# RPi-HAT_BUS-Controller_V0_9c.net
KiCad netlist of a schematic drawn in EAGLE
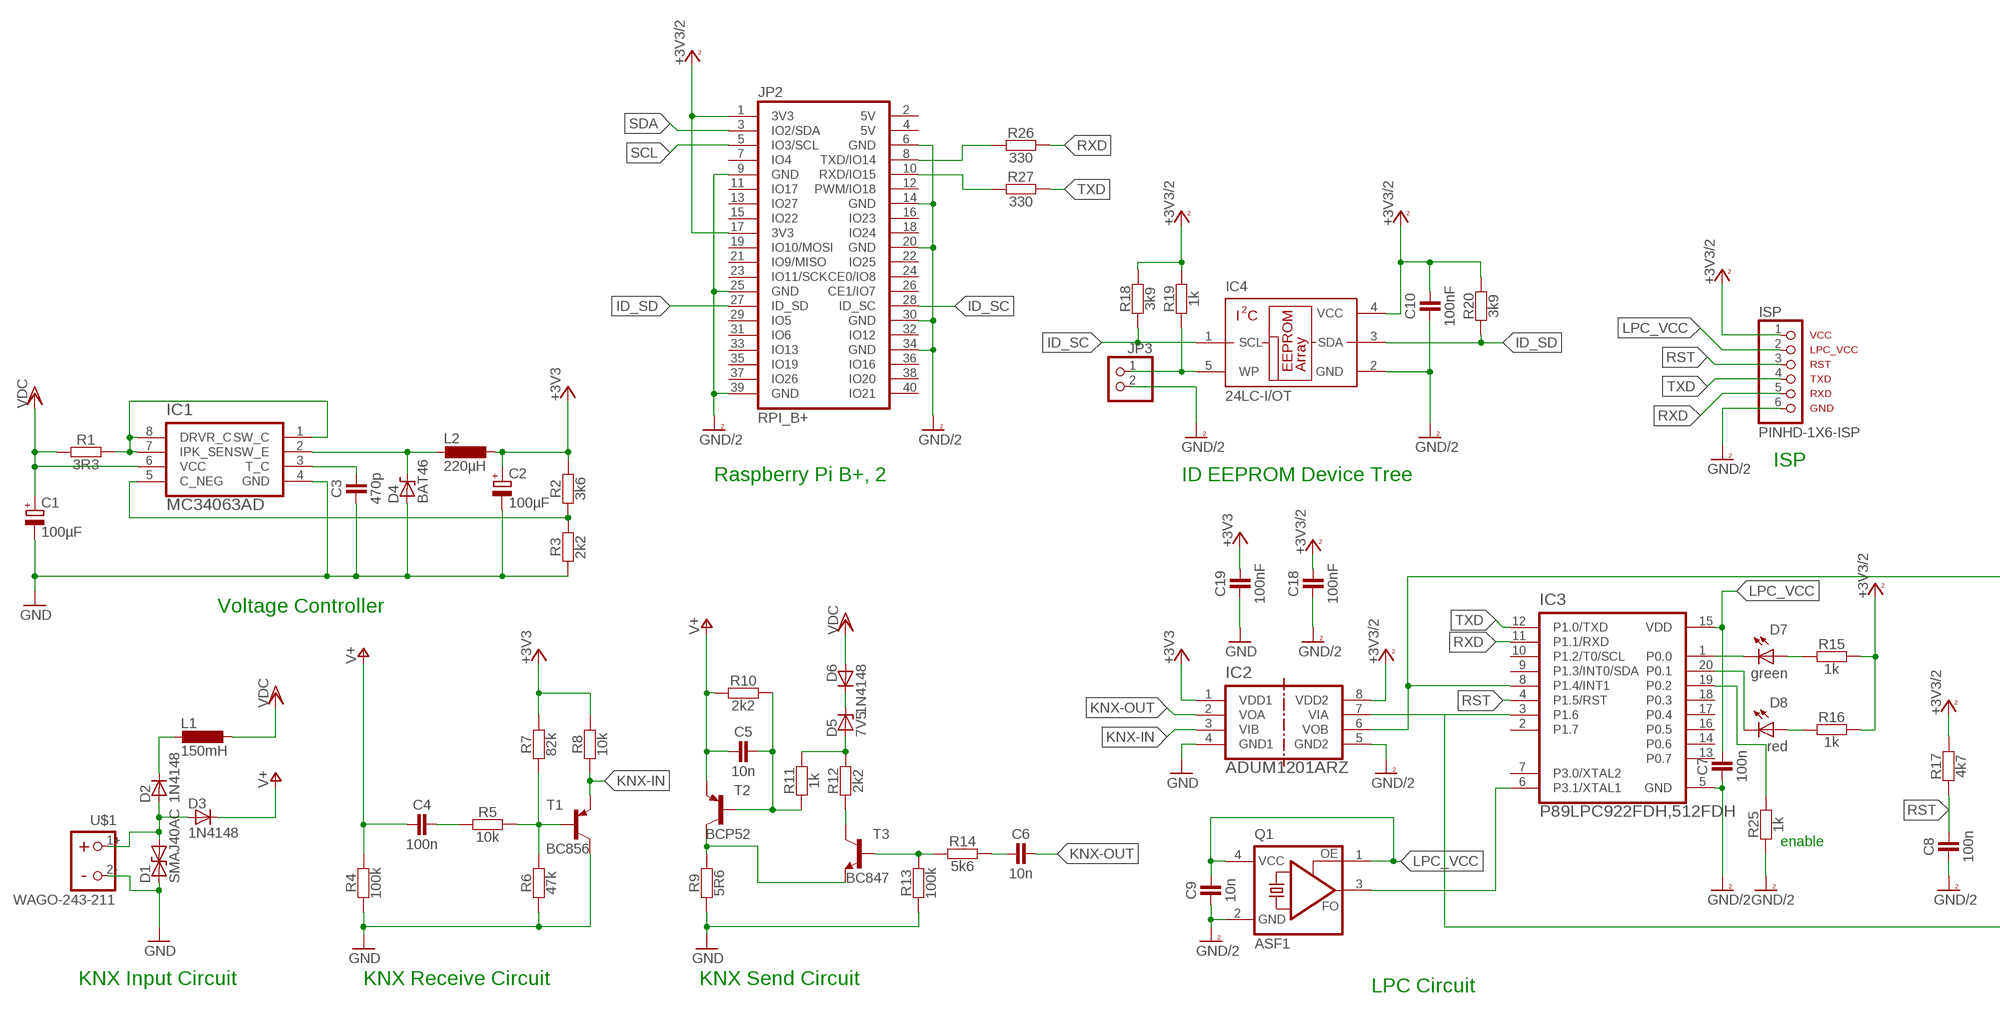
[diagram p0: schematic, sheet 1, part 1 of 2]
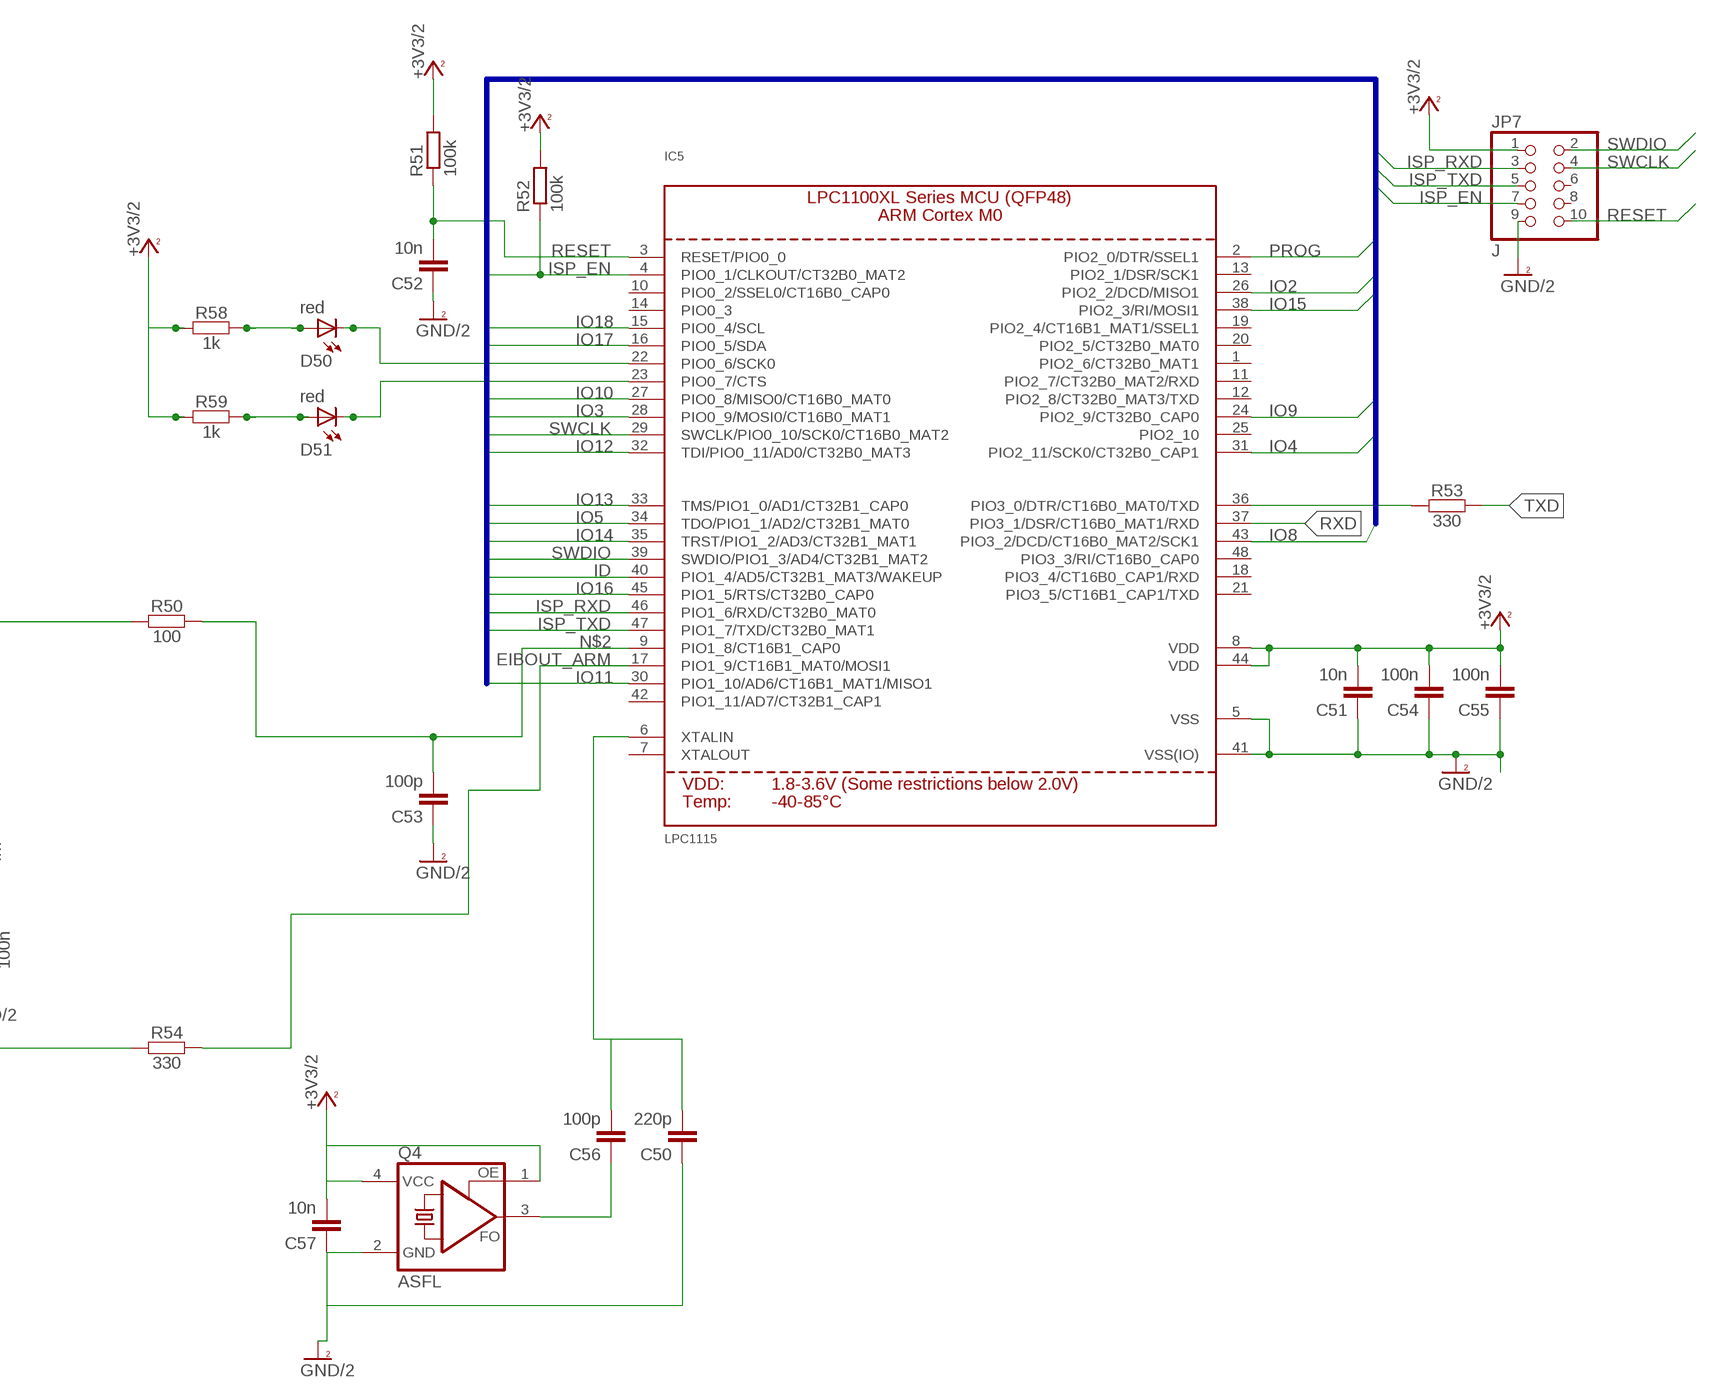
[diagram p1: schematic, sheet 1, part 2 of 2]

(export (version "E")
  (design (tool "Eeschema 10.0.6"))
  (components
    (comp (ref "C1")
      (value "100µF")
      (footprint "eagle-import:PANASONIC_D")
      (libsource (lib "eagle-import") (part "100µF,35V"))
    )
    (comp (ref "C2")
      (value "100µF")
      (footprint "eagle-import:PANASONIC_C")
      (libsource (lib "eagle-import") (part "100µF,6.3V"))
    )
    (comp (ref "C3")
      (value "470p")
      (footprint "eagle-import:R1206")
      (libsource (lib "eagle-import") (part "CAPACITORC1206"))
    )
    (comp (ref "C4")
      (value "100n")
      (footprint "eagle-import:R1206")
      (libsource (lib "eagle-import") (part "CAPACITORC1206"))
    )
    (comp (ref "C5")
      (value "10n")
      (footprint "eagle-import:R1206")
      (libsource (lib "eagle-import") (part "CAPACITORC1206"))
    )
    (comp (ref "C6")
      (value "10n")
      (footprint "eagle-import:R1206")
      (libsource (lib "eagle-import") (part "CAPACITORC1206"))
    )
    (comp (ref "C7")
      (value "100n")
      (footprint "eagle-import:R1206")
      (libsource (lib "eagle-import") (part "CAPACITORC1206"))
    )
    (comp (ref "C8")
      (value "100n")
      (footprint "eagle-import:R1206")
      (libsource (lib "eagle-import") (part "CAPACITORC1206"))
    )
    (comp (ref "C9")
      (value "10n")
      (footprint "eagle-import:R1206")
      (libsource (lib "eagle-import") (part "CAPACITORC1206"))
    )
    (comp (ref "C10")
      (value "100nF")
      (footprint "eagle-import:R1206")
      (libsource (lib "eagle-import") (part "CAPACITORC1206"))
    )
    (comp (ref "C18")
      (value "100nF")
      (footprint "eagle-import:R1206")
      (libsource (lib "eagle-import") (part "CAPACITORC1206"))
    )
    (comp (ref "C19")
      (value "100nF")
      (footprint "eagle-import:R1206")
      (libsource (lib "eagle-import") (part "CAPACITORC1206"))
    )
    (comp (ref "C50")
      (value "220p")
      (footprint "eagle-import:C1206")
      (libsource (lib "eagle-import") (part "C-EUC1206"))
    )
    (comp (ref "C51")
      (value "10n")
      (footprint "eagle-import:C1206")
      (libsource (lib "eagle-import") (part "C-EUC1206"))
    )
    (comp (ref "C52")
      (value "10n")
      (footprint "eagle-import:C1206")
      (libsource (lib "eagle-import") (part "C-EUC1206"))
    )
    (comp (ref "C53")
      (value "100p")
      (footprint "eagle-import:C1206")
      (libsource (lib "eagle-import") (part "C-EUC1206"))
    )
    (comp (ref "C54")
      (value "100n")
      (footprint "eagle-import:C1206")
      (libsource (lib "eagle-import") (part "C-EUC1206"))
    )
    (comp (ref "C55")
      (value "100n")
      (footprint "eagle-import:C1206")
      (libsource (lib "eagle-import") (part "C-EUC1206"))
    )
    (comp (ref "C56")
      (value "100p")
      (footprint "eagle-import:C1206")
      (libsource (lib "eagle-import") (part "C-EUC1206"))
    )
    (comp (ref "C57")
      (value "10n")
      (footprint "eagle-import:C1206")
      (libsource (lib "eagle-import") (part "C-EUC1206"))
    )
    (comp (ref "D1")
      (value "SMAJ40AC")
      (footprint "eagle-import:DO-214AC")
      (libsource (lib "eagle-import") (part "SMAJ40AC"))
    )
    (comp (ref "D2")
      (value "1N4148")
      (footprint "eagle-import:MINIMELF")
      (libsource (lib "eagle-import") (part "1N4148MINIMELF"))
    )
    (comp (ref "D3")
      (value "1N4148")
      (footprint "eagle-import:MINIMELF")
      (libsource (lib "eagle-import") (part "1N4148MINIMELF"))
    )
    (comp (ref "D4")
      (value "BAT46")
      (footprint "eagle-import:MINIMELF")
      (libsource (lib "eagle-import") (part "BAT46"))
    )
    (comp (ref "D5")
      (value "7V5")
      (footprint "eagle-import:MINIMELF")
      (libsource (lib "eagle-import") (part "Z-DIODE"))
    )
    (comp (ref "D6")
      (value "1N4148")
      (footprint "eagle-import:MINIMELF")
      (libsource (lib "eagle-import") (part "Diode_for_Selfbus-Projects_1N4148MINIMELF"))
    )
    (comp (ref "D7")
      (value "green")
      (footprint "eagle-import:CHIPLED_1206")
      (libsource (lib "eagle-import") (part "LED1206"))
    )
    (comp (ref "D8")
      (value "red")
      (footprint "eagle-import:CHIPLED_1206")
      (libsource (lib "eagle-import") (part "LED1206"))
    )
    (comp (ref "D50")
      (value "red")
      (footprint "eagle-import:CHIPLED_1206")
      (libsource (lib "eagle-import") (part "LED1206"))
    )
    (comp (ref "D51")
      (value "red")
      (footprint "eagle-import:CHIPLED_1206")
      (libsource (lib "eagle-import") (part "LED1206"))
    )
    (comp (ref "IC1")
      (value "MC34063AD")
      (footprint "eagle-import:SOIC127P600X175-8N")
      (libsource (lib "eagle-import") (part "MC34063AD"))
    )
    (comp (ref "IC2")
      (value "ADUM1201ARZ")
      (footprint "eagle-import:SOIC127P600X175-8N")
      (libsource (lib "eagle-import") (part "ADUM1201ARZ"))
    )
    (comp (ref "IC3")
      (value "P89LPC922FDH,512FDH")
      (footprint "eagle-import:SOP65P640X110-20N")
      (fields (field (name "MPN") "P89LPC922FDH,512"))
      (libsource (lib "eagle-import") (part "P89LPC922FDH,512FDH"))
    )
    (comp (ref "IC4")
      (value "24LC-I/OT")
      (footprint "eagle-import:SOT23-5")
      (libsource (lib "eagle-import") (part "24LC-I/OT"))
    )
    (comp (ref "IC5")
      (value "LPC1115")
      (footprint "eagle-import:LQFP48")
      (libsource (lib "eagle-import") (part "LPC1113/4/5_QFP48_XLSERIES"))
    )
    (comp (ref "ISP")
      (value "PINHD-1X6-ISP")
      (footprint "eagle-import:1X06")
      (libsource (lib "eagle-import") (part "PINHD-1X6-ISP"))
    )
    (comp (ref "JP2")
      (value "RPI_B+")
      (footprint "eagle-import:RPI-B+HAT")
      (libsource (lib "eagle-import") (part "RPI_B+"))
    )
    (comp (ref "JP3")
      (value "PINHD-1X2")
      (footprint "eagle-import:1X02")
      (libsource (lib "eagle-import") (part "PINHD-1X2"))
    )
    (comp (ref "JP7")
      (value "J")
      (footprint "eagle-import:2X05M")
      (libsource (lib "eagle-import") (part "PINHD-2X05_2.00"))
    )
    (comp (ref "L1")
      (value "150mH")
      (footprint "eagle-import:11P-L1")
      (libsource (lib "eagle-import") (part "150MH-L11PL1"))
    )
    (comp (ref "L2")
      (value "220µH")
      (footprint "eagle-import:2200-11.43")
      (libsource (lib "eagle-import") (part "220µH-SMCC11.43"))
    )
    (comp (ref "Q1")
      (value "ASF1")
      (footprint "eagle-import:ASF")
      (libsource (lib "eagle-import") (part "ASF1"))
    )
    (comp (ref "Q4")
      (value "ASFL")
      (footprint "eagle-import:ASF")
      (fields (field (name "MPN") "ASFLM1-50.000MHZ-C-T"))
      (libsource (lib "eagle-import") (part "crystal_ASFL"))
    )
    (comp (ref "R1")
      (value "3R3")
      (footprint "eagle-import:R1206")
      (libsource (lib "eagle-import") (part "RESISTORR1206"))
    )
    (comp (ref "R2")
      (value "3k6")
      (footprint "eagle-import:R1206")
      (libsource (lib "eagle-import") (part "RESISTORR1206"))
    )
    (comp (ref "R3")
      (value "2k2")
      (footprint "eagle-import:R1206")
      (libsource (lib "eagle-import") (part "RESISTORR1206"))
    )
    (comp (ref "R4")
      (value "100k")
      (footprint "eagle-import:R1206")
      (libsource (lib "eagle-import") (part "RESISTORR1206"))
    )
    (comp (ref "R5")
      (value "10k")
      (footprint "eagle-import:R1206")
      (libsource (lib "eagle-import") (part "RESISTORR1206"))
    )
    (comp (ref "R6")
      (value "47k")
      (footprint "eagle-import:R1206")
      (libsource (lib "eagle-import") (part "RESISTORR1206"))
    )
    (comp (ref "R7")
      (value "82k")
      (footprint "eagle-import:R1206")
      (libsource (lib "eagle-import") (part "RESISTORR1206"))
    )
    (comp (ref "R8")
      (value "10k")
      (footprint "eagle-import:R1206")
      (libsource (lib "eagle-import") (part "RESISTORR1206"))
    )
    (comp (ref "R9")
      (value "5R6")
      (footprint "eagle-import:R1206")
      (libsource (lib "eagle-import") (part "RESISTORR1206"))
    )
    (comp (ref "R10")
      (value "2k2")
      (footprint "eagle-import:R1206")
      (libsource (lib "eagle-import") (part "RESISTORR1206"))
    )
    (comp (ref "R11")
      (value "1k")
      (footprint "eagle-import:R1206")
      (libsource (lib "eagle-import") (part "RESISTORR1206"))
    )
    (comp (ref "R12")
      (value "2k2")
      (footprint "eagle-import:R1206")
      (libsource (lib "eagle-import") (part "RESISTORR1206"))
    )
    (comp (ref "R13")
      (value "100k")
      (footprint "eagle-import:R1206")
      (libsource (lib "eagle-import") (part "RESISTORR1206"))
    )
    (comp (ref "R14")
      (value "5k6")
      (footprint "eagle-import:R1206")
      (libsource (lib "eagle-import") (part "RESISTORR1206"))
    )
    (comp (ref "R15")
      (value "1k")
      (footprint "eagle-import:R1206")
      (libsource (lib "eagle-import") (part "RESISTORR1206"))
    )
    (comp (ref "R16")
      (value "1k")
      (footprint "eagle-import:R1206")
      (libsource (lib "eagle-import") (part "RESISTORR1206"))
    )
    (comp (ref "R17")
      (value "4k7")
      (footprint "eagle-import:R1206")
      (libsource (lib "eagle-import") (part "RESISTORR1206"))
    )
    (comp (ref "R18")
      (value "3k9")
      (footprint "eagle-import:R1206")
      (libsource (lib "eagle-import") (part "RESISTORR1206"))
    )
    (comp (ref "R19")
      (value "1k")
      (footprint "eagle-import:R1206")
      (libsource (lib "eagle-import") (part "RESISTORR1206"))
    )
    (comp (ref "R20")
      (value "3k9")
      (footprint "eagle-import:R1206")
      (libsource (lib "eagle-import") (part "RESISTORR1206"))
    )
    (comp (ref "R25")
      (value "1k")
      (footprint "eagle-import:R1206")
      (libsource (lib "eagle-import") (part "RESISTORR1206"))
    )
    (comp (ref "R26")
      (value "330")
      (footprint "eagle-import:R1206")
      (libsource (lib "eagle-import") (part "RESISTORR1206"))
    )
    (comp (ref "R27")
      (value "330")
      (footprint "eagle-import:R1206")
      (libsource (lib "eagle-import") (part "RESISTORR1206"))
    )
    (comp (ref "R50")
      (value "100")
      (footprint "eagle-import:R1206")
      (libsource (lib "eagle-import") (part "RESISTORR1206"))
    )
    (comp (ref "R51")
      (value "100k")
      (footprint "eagle-import:R1206")
      (libsource (lib "eagle-import") (part "R-EU_R1206"))
    )
    (comp (ref "R52")
      (value "100k")
      (footprint "eagle-import:R1206")
      (libsource (lib "eagle-import") (part "R-EU_R1206"))
    )
    (comp (ref "R53")
      (value "330")
      (footprint "eagle-import:R1206")
      (libsource (lib "eagle-import") (part "RESISTORR1206"))
    )
    (comp (ref "R54")
      (value "330")
      (footprint "eagle-import:R1206")
      (libsource (lib "eagle-import") (part "RESISTORR1206"))
    )
    (comp (ref "R58")
      (value "1k")
      (footprint "eagle-import:R1206")
      (libsource (lib "eagle-import") (part "RESISTORR1206"))
    )
    (comp (ref "R59")
      (value "1k")
      (footprint "eagle-import:R1206")
      (libsource (lib "eagle-import") (part "RESISTORR1206"))
    )
    (comp (ref "T1")
      (value "BC856")
      (footprint "eagle-import:SOT23")
      (libsource (lib "eagle-import") (part "PNPBC856"))
    )
    (comp (ref "T2")
      (value "BCP52")
      (footprint "eagle-import:SOT223")
      (libsource (lib "eagle-import") (part "PNPBCP52"))
    )
    (comp (ref "T3")
      (value "BC847")
      (footprint "eagle-import:SOT23")
      (libsource (lib "eagle-import") (part "NPN-BC847"))
    )
    (comp (ref "U$1")
      (value "WAGO-243-211")
      (footprint "eagle-import:WAGO-243-211")
      (libsource (lib "eagle-import") (part "WAGO-243-211"))
    )
  )
  (nets
    (net (code "1") (name "+3V3") (class "Default")
      (node (ref "C19") (pin "2") (pinfunction "2_2") (pintype "passive"))
      (node (ref "C2") (pin "+") (pinfunction "+_+") (pintype "passive"))
      (node (ref "IC2") (pin "1") (pinfunction "VDD1_1") (pintype "power_in"))
      (node (ref "L2") (pin "1") (pinfunction "1_1") (pintype "passive"))
      (node (ref "R2") (pin "2") (pinfunction "2_2") (pintype "passive"))
      (node (ref "R7") (pin "2") (pinfunction "2_2") (pintype "passive"))
      (node (ref "R8") (pin "2") (pinfunction "2_2") (pintype "passive"))
    )
    (net (code "2") (name "+3V3{slash}2") (class "Default")
      (node (ref "C10") (pin "2") (pinfunction "2_2") (pintype "passive"))
      (node (ref "C18") (pin "2") (pinfunction "2_2") (pintype "passive"))
      (node (ref "C51") (pin "2") (pinfunction "2_2") (pintype "passive"))
      (node (ref "C54") (pin "2") (pinfunction "2_2") (pintype "passive"))
      (node (ref "C55") (pin "2") (pinfunction "2_2") (pintype "passive"))
      (node (ref "C57") (pin "2") (pinfunction "2_2") (pintype "passive"))
      (node (ref "IC2") (pin "8") (pinfunction "VDD2_8") (pintype "power_in"))
      (node (ref "IC4") (pin "4") (pinfunction "VCC_4") (pintype "power_in"))
      (node (ref "IC5") (pin "44") (pinfunction "VDD_44") (pintype "power_in"))
      (node (ref "IC5") (pin "8") (pinfunction "VDD_8") (pintype "power_in"))
      (node (ref "ISP") (pin "1") (pinfunction "1_1") (pintype "passive"))
      (node (ref "JP2") (pin "1") (pinfunction "3V3_1") (pintype "passive"))
      (node (ref "JP2") (pin "17") (pinfunction "3V3_17") (pintype "passive"))
      (node (ref "JP7") (pin "1") (pinfunction "1_1") (pintype "passive"))
      (node (ref "Q4") (pin "1") (pinfunction "OE_1") (pintype "input"))
      (node (ref "Q4") (pin "4") (pinfunction "VCC_4") (pintype "power_in"))
      (node (ref "R15") (pin "2") (pinfunction "2_2") (pintype "passive"))
      (node (ref "R16") (pin "2") (pinfunction "2_2") (pintype "passive"))
      (node (ref "R17") (pin "2") (pinfunction "2_2") (pintype "passive"))
      (node (ref "R18") (pin "2") (pinfunction "2_2") (pintype "passive"))
      (node (ref "R19") (pin "2") (pinfunction "2_2") (pintype "passive"))
      (node (ref "R20") (pin "2") (pinfunction "2_2") (pintype "passive"))
      (node (ref "R51") (pin "2") (pinfunction "2_2") (pintype "passive"))
      (node (ref "R52") (pin "2") (pinfunction "2_2") (pintype "passive"))
      (node (ref "R58") (pin "1") (pinfunction "1_1") (pintype "passive"))
      (node (ref "R59") (pin "1") (pinfunction "1_1") (pintype "passive"))
    )
    (net (code "3") (name "/EIBOUT_ARM") (class "Default")
      (node (ref "IC5") (pin "17") (pinfunction "PIO1_9/CT16B1_MAT0/MOSI1_17") (pintype "bidirectional"))
      (node (ref "R54") (pin "2") (pinfunction "2_2") (pintype "passive"))
    )
    (net (code "4") (name "/ID") (class "Default")
      (node (ref "IC5") (pin "40") (pinfunction "PIO1_4/AD5/CT32B1_MAT3/WAKEUP_40") (pintype "bidirectional"))
    )
    (net (code "5") (name "/IO2") (class "Default")
      (node (ref "IC5") (pin "26") (pinfunction "PIO2_2/DCD/MISO1_26") (pintype "bidirectional"))
    )
    (net (code "6") (name "/IO3") (class "Default")
      (node (ref "IC5") (pin "28") (pinfunction "PIO0_9/MOSI0/CT16B0_MAT1_28") (pintype "bidirectional"))
    )
    (net (code "7") (name "/IO4") (class "Default")
      (node (ref "IC5") (pin "31") (pinfunction "PIO2_11/SCK0/CT32B0_CAP1_31") (pintype "bidirectional"))
    )
    (net (code "8") (name "/IO5") (class "Default")
      (node (ref "IC5") (pin "34") (pinfunction "TDO/PIO1_1/AD2/CT32B1_MAT0_34") (pintype "bidirectional"))
    )
    (net (code "9") (name "/IO8") (class "Default")
      (node (ref "IC5") (pin "43") (pinfunction "PIO3_2/DCD/CT16B0_MAT2/SCK1_43") (pintype "bidirectional"))
    )
    (net (code "10") (name "/IO9") (class "Default")
      (node (ref "IC5") (pin "24") (pinfunction "PIO2_9/CT32B0_CAP0_24") (pintype "bidirectional"))
    )
    (net (code "11") (name "/IO10") (class "Default")
      (node (ref "IC5") (pin "27") (pinfunction "PIO0_8/MISO0/CT16B0_MAT0_27") (pintype "bidirectional"))
    )
    (net (code "12") (name "/IO11") (class "Default")
      (node (ref "IC5") (pin "30") (pinfunction "PIO1_10/AD6/CT16B1_MAT1/MISO1_30") (pintype "bidirectional"))
    )
    (net (code "13") (name "/IO12") (class "Default")
      (node (ref "IC5") (pin "32") (pinfunction "TDI/PIO0_11/AD0/CT32B0_MAT3_32") (pintype "bidirectional"))
    )
    (net (code "14") (name "/IO13") (class "Default")
      (node (ref "IC5") (pin "33") (pinfunction "TMS/PIO1_0/AD1/CT32B1_CAP0_33") (pintype "bidirectional"))
    )
    (net (code "15") (name "/IO14") (class "Default")
      (node (ref "IC5") (pin "35") (pinfunction "TRST/PIO1_2/AD3/CT32B1_MAT1_35") (pintype "bidirectional"))
    )
    (net (code "16") (name "/IO15") (class "Default")
      (node (ref "IC5") (pin "38") (pinfunction "PIO2_3/RI/MOSI1_38") (pintype "bidirectional"))
    )
    (net (code "17") (name "/IO16") (class "Default")
      (node (ref "IC5") (pin "45") (pinfunction "PIO1_5/RTS/CT32B0_CAP0_45") (pintype "bidirectional"))
    )
    (net (code "18") (name "/IO17") (class "Default")
      (node (ref "IC5") (pin "16") (pinfunction "PIO0_5/SDA_16") (pintype "bidirectional"))
    )
    (net (code "19") (name "/IO18") (class "Default")
      (node (ref "IC5") (pin "15") (pinfunction "PIO0_4/SCL_15") (pintype "bidirectional"))
    )
    (net (code "20") (name "/ISP_EN") (class "Default")
      (node (ref "IC5") (pin "4") (pinfunction "PIO0_1/CLKOUT/CT32B0_MAT2_4") (pintype "bidirectional"))
      (node (ref "JP7") (pin "7") (pinfunction "7_7") (pintype "passive"))
      (node (ref "R52") (pin "1") (pinfunction "1_1") (pintype "passive"))
    )
    (net (code "21") (name "/ISP_RXD") (class "Default")
      (node (ref "IC5") (pin "46") (pinfunction "PIO1_6/RXD/CT32B0_MAT0_46") (pintype "bidirectional"))
      (node (ref "JP7") (pin "3") (pinfunction "3_3") (pintype "passive"))
    )
    (net (code "22") (name "/ISP_TXD") (class "Default")
      (node (ref "IC5") (pin "47") (pinfunction "PIO1_7/TXD/CT32B0_MAT1_47") (pintype "bidirectional"))
      (node (ref "JP7") (pin "5") (pinfunction "5_5") (pintype "passive"))
    )
    (net (code "23") (name "/N$2") (class "Default")
      (node (ref "C53") (pin "2") (pinfunction "2_2") (pintype "passive"))
      (node (ref "IC5") (pin "9") (pinfunction "PIO1_8/CT16B1_CAP0_9") (pintype "bidirectional"))
      (node (ref "R50") (pin "2") (pinfunction "2_2") (pintype "passive"))
    )
    (net (code "24") (name "/PROG") (class "Default")
      (node (ref "IC5") (pin "2") (pinfunction "PIO2_0/DTR/SSEL1_2") (pintype "bidirectional"))
    )
    (net (code "25") (name "/RESET") (class "Default")
      (node (ref "C52") (pin "2") (pinfunction "2_2") (pintype "passive"))
      (node (ref "IC5") (pin "3") (pinfunction "RESET/PIO0_0_3") (pintype "bidirectional"))
      (node (ref "JP7") (pin "10") (pinfunction "10_10") (pintype "passive"))
      (node (ref "R51") (pin "1") (pinfunction "1_1") (pintype "passive"))
    )
    (net (code "26") (name "/SWCLK") (class "Default")
      (node (ref "IC5") (pin "29") (pinfunction "SWCLK/PIO0_10/SCK0/CT16B0_MAT2_29") (pintype "bidirectional"))
      (node (ref "JP7") (pin "4") (pinfunction "4_4") (pintype "passive"))
    )
    (net (code "27") (name "/SWDIO") (class "Default")
      (node (ref "IC5") (pin "39") (pinfunction "SWDIO/PIO1_3/AD4/CT32B1_MAT2_39") (pintype "bidirectional"))
      (node (ref "JP7") (pin "2") (pinfunction "2_2") (pintype "passive"))
    )
    (net (code "28") (name "GND") (class "Default")
      (node (ref "C1") (pin "-") (pinfunction "-_-") (pintype "passive"))
      (node (ref "C19") (pin "1") (pinfunction "1_1") (pintype "passive"))
      (node (ref "C2") (pin "-") (pinfunction "-_-") (pintype "passive"))
      (node (ref "C3") (pin "1") (pinfunction "1_1") (pintype "passive"))
      (node (ref "D1") (pin "A") (pinfunction "A_A") (pintype "passive"))
      (node (ref "D4") (pin "A") (pinfunction "A_A") (pintype "passive"))
      (node (ref "IC1") (pin "4") (pinfunction "GND_4") (pintype "passive"))
      (node (ref "IC2") (pin "4") (pinfunction "GND1_4") (pintype "passive"))
      (node (ref "R13") (pin "1") (pinfunction "1_1") (pintype "passive"))
      (node (ref "R3") (pin "1") (pinfunction "1_1") (pintype "passive"))
      (node (ref "R4") (pin "1") (pinfunction "1_1") (pintype "passive"))
      (node (ref "R6") (pin "1") (pinfunction "1_1") (pintype "passive"))
      (node (ref "R9") (pin "1") (pinfunction "1_1") (pintype "passive"))
      (node (ref "T1") (pin "3") (pinfunction "C_3") (pintype "passive"))
      (node (ref "U$1") (pin "2-") (pinfunction "2-_2-") (pintype "passive"))
    )
    (net (code "29") (name "GND{slash}2") (class "Default")
      (node (ref "C10") (pin "1") (pinfunction "1_1") (pintype "passive"))
      (node (ref "C18") (pin "1") (pinfunction "1_1") (pintype "passive"))
      (node (ref "C50") (pin "1") (pinfunction "1_1") (pintype "passive"))
      (node (ref "C51") (pin "1") (pinfunction "1_1") (pintype "passive"))
      (node (ref "C52") (pin "1") (pinfunction "1_1") (pintype "passive"))
      (node (ref "C53") (pin "1") (pinfunction "1_1") (pintype "passive"))
      (node (ref "C54") (pin "1") (pinfunction "1_1") (pintype "passive"))
      (node (ref "C55") (pin "1") (pinfunction "1_1") (pintype "passive"))
      (node (ref "C57") (pin "1") (pinfunction "1_1") (pintype "passive"))
      (node (ref "C7") (pin "1") (pinfunction "1_1") (pintype "passive"))
      (node (ref "C8") (pin "1") (pinfunction "1_1") (pintype "passive"))
      (node (ref "C9") (pin "1") (pinfunction "1_1") (pintype "passive"))
      (node (ref "IC2") (pin "5") (pinfunction "GND2_5") (pintype "passive"))
      (node (ref "IC3") (pin "5") (pinfunction "GND_5") (pintype "passive"))
      (node (ref "IC4") (pin "2") (pinfunction "GND_2") (pintype "power_in"))
      (node (ref "IC5") (pin "41") (pinfunction "VSS(IO)_41") (pintype "power_in"))
      (node (ref "IC5") (pin "5") (pinfunction "VSS_5") (pintype "power_in"))
      (node (ref "ISP") (pin "6") (pinfunction "6_6") (pintype "passive"))
      (node (ref "JP2") (pin "14") (pinfunction "GND_14") (pintype "passive"))
      (node (ref "JP2") (pin "20") (pinfunction "GND_20") (pintype "passive"))
      (node (ref "JP2") (pin "25") (pinfunction "GND_25") (pintype "passive"))
      (node (ref "JP2") (pin "30") (pinfunction "GND_30") (pintype "bidirectional"))
      (node (ref "JP2") (pin "34") (pinfunction "GND_34") (pintype "bidirectional"))
      (node (ref "JP2") (pin "39") (pinfunction "GND_39") (pintype "bidirectional"))
      (node (ref "JP2") (pin "6") (pinfunction "GND_6") (pintype "passive"))
      (node (ref "JP2") (pin "9") (pinfunction "GND_9") (pintype "passive"))
      (node (ref "JP3") (pin "2") (pinfunction "2_2") (pintype "passive"))
      (node (ref "JP7") (pin "9") (pinfunction "9_9") (pintype "passive"))
      (node (ref "Q1") (pin "2") (pinfunction "GND_2") (pintype "power_in"))
      (node (ref "Q4") (pin "2") (pinfunction "GND_2") (pintype "power_in"))
      (node (ref "R25") (pin "1") (pinfunction "1_1") (pintype "passive"))
    )
    (net (code "30") (name "ID_SC") (class "Default")
      (node (ref "IC4") (pin "1") (pinfunction "SCL_1") (pintype "bidirectional"))
      (node (ref "JP2") (pin "28") (pinfunction "ID_SC_28") (pintype "bidirectional"))
      (node (ref "R18") (pin "1") (pinfunction "1_1") (pintype "passive"))
    )
    (net (code "31") (name "ID_SD") (class "Default")
      (node (ref "IC4") (pin "3") (pinfunction "SDA_3") (pintype "bidirectional"))
      (node (ref "JP2") (pin "27") (pinfunction "ID_SD_27") (pintype "bidirectional"))
      (node (ref "R20") (pin "1") (pinfunction "1_1") (pintype "passive"))
    )
    (net (code "32") (name "KNX-IN") (class "Default")
      (node (ref "IC2") (pin "3") (pinfunction "VIB_3") (pintype "input"))
      (node (ref "R8") (pin "1") (pinfunction "1_1") (pintype "passive"))
      (node (ref "T1") (pin "2") (pinfunction "E_2") (pintype "passive"))
    )
    (net (code "33") (name "KNX-OUT") (class "Default")
      (node (ref "C6") (pin "2") (pinfunction "2_2") (pintype "passive"))
      (node (ref "IC2") (pin "2") (pinfunction "VOA_2") (pintype "output"))
    )
    (net (code "34") (name "LPC_VCC") (class "Default")
      (node (ref "C7") (pin "2") (pinfunction "2_2") (pintype "passive"))
      (node (ref "C9") (pin "2") (pinfunction "2_2") (pintype "passive"))
      (node (ref "IC3") (pin "15") (pinfunction "VDD_15") (pintype "power_in"))
      (node (ref "ISP") (pin "2") (pinfunction "2_2") (pintype "passive"))
      (node (ref "Q1") (pin "1") (pinfunction "OE_1") (pintype "input"))
      (node (ref "Q1") (pin "4") (pinfunction "VCC_4") (pintype "power_in"))
    )
    (net (code "35") (name "Net-(C4-Pad2)") (class "Default")
      (node (ref "C4") (pin "2") (pinfunction "2_2") (pintype "passive"))
      (node (ref "R5") (pin "1") (pinfunction "1_1") (pintype "passive"))
    )
    (net (code "36") (name "Net-(C6-Pad1)") (class "Default")
      (node (ref "C6") (pin "1") (pinfunction "1_1") (pintype "passive"))
      (node (ref "R14") (pin "2") (pinfunction "2_2") (pintype "passive"))
    )
    (net (code "37") (name "Net-(D1-PadC)") (class "Default")
      (node (ref "D1") (pin "C") (pinfunction "C_C") (pintype "passive"))
      (node (ref "D2") (pin "A") (pinfunction "A_A") (pintype "passive"))
      (node (ref "D3") (pin "A") (pinfunction "A_A") (pintype "passive"))
      (node (ref "U$1") (pin "1+") (pinfunction "1+_1+") (pintype "passive"))
    )
    (net (code "38") (name "Net-(D2-PadC)") (class "Default")
      (node (ref "D2") (pin "C") (pinfunction "C_C") (pintype "passive"))
      (node (ref "L1") (pin "2") (pinfunction "2_2") (pintype "passive"))
    )
    (net (code "39") (name "Net-(D5-PadA)") (class "Default")
      (node (ref "D5") (pin "A") (pinfunction "A_A") (pintype "passive"))
      (node (ref "R11") (pin "2") (pinfunction "2_2") (pintype "passive"))
      (node (ref "R12") (pin "2") (pinfunction "2_2") (pintype "passive"))
    )
    (net (code "40") (name "Net-(D5-PadC)") (class "Default")
      (node (ref "D5") (pin "C") (pinfunction "C_C") (pintype "passive"))
      (node (ref "D6") (pin "C") (pinfunction "C_C") (pintype "passive"))
    )
    (net (code "41") (name "Net-(D7-PadA)") (class "Default")
      (node (ref "D7") (pin "A") (pinfunction "A_A") (pintype "passive"))
      (node (ref "R15") (pin "1") (pinfunction "1_1") (pintype "passive"))
    )
    (net (code "42") (name "Net-(D8-PadA)") (class "Default")
      (node (ref "D8") (pin "A") (pinfunction "A_A") (pintype "passive"))
      (node (ref "R16") (pin "1") (pinfunction "1_1") (pintype "passive"))
    )
    (net (code "43") (name "Net-(D50-PadA)") (class "Default")
      (node (ref "D50") (pin "A") (pinfunction "A_A") (pintype "passive"))
      (node (ref "R58") (pin "2") (pinfunction "2_2") (pintype "passive"))
    )
    (net (code "44") (name "Net-(D51-PadA)") (class "Default")
      (node (ref "D51") (pin "A") (pinfunction "A_A") (pintype "passive"))
      (node (ref "R59") (pin "2") (pinfunction "2_2") (pintype "passive"))
    )
    (net (code "45") (name "Net-(IC1-C_NEG)") (class "Default")
      (node (ref "IC1") (pin "5") (pinfunction "C_NEG_5") (pintype "input"))
      (node (ref "R2") (pin "1") (pinfunction "1_1") (pintype "passive"))
      (node (ref "R3") (pin "2") (pinfunction "2_2") (pintype "passive"))
    )
    (net (code "46") (name "Net-(IC1-DRVR_C)") (class "Default")
      (node (ref "IC1") (pin "1") (pinfunction "SW_C_1") (pintype "output"))
      (node (ref "IC1") (pin "7") (pinfunction "IPK_SEN_7") (pintype "input"))
      (node (ref "IC1") (pin "8") (pinfunction "DRVR_C_8") (pintype "input"))
      (node (ref "R1") (pin "2") (pinfunction "2_2") (pintype "passive"))
    )
    (net (code "47") (name "Net-(IC1-SW_E)") (class "Default")
      (node (ref "D4") (pin "C") (pinfunction "C_C") (pintype "passive"))
      (node (ref "IC1") (pin "2") (pinfunction "SW_E_2") (pintype "output"))
      (node (ref "L2") (pin "2") (pinfunction "2_2") (pintype "passive"))
    )
    (net (code "48") (name "Net-(IC1-T_C)") (class "Default")
      (node (ref "C3") (pin "2") (pinfunction "2_2") (pintype "passive"))
      (node (ref "IC1") (pin "3") (pinfunction "T_C_3") (pintype "output"))
    )
    (net (code "49") (name "Net-(IC2-VIA)") (class "Default")
      (node (ref "IC2") (pin "7") (pinfunction "VIA_7") (pintype "input"))
      (node (ref "IC3") (pin "3") (pinfunction "P1.6_3") (pintype "bidirectional"))
      (node (ref "R54") (pin "1") (pinfunction "1_1") (pintype "passive"))
    )
    (net (code "50") (name "Net-(IC2-VOB)") (class "Default")
      (node (ref "IC2") (pin "6") (pinfunction "VOB_6") (pintype "output"))
      (node (ref "IC3") (pin "8") (pinfunction "P1.4/INT1_8") (pintype "bidirectional"))
      (node (ref "R50") (pin "1") (pinfunction "1_1") (pintype "passive"))
    )
    (net (code "51") (name "Net-(IC3-P0.0)") (class "Default")
      (node (ref "D7") (pin "C") (pinfunction "C_C") (pintype "passive"))
      (node (ref "IC3") (pin "1") (pinfunction "P0.0_1") (pintype "bidirectional"))
    )
    (net (code "52") (name "Net-(IC3-P0.1)") (class "Default")
      (node (ref "D8") (pin "C") (pinfunction "C_C") (pintype "passive"))
      (node (ref "IC3") (pin "20") (pinfunction "P0.1_20") (pintype "bidirectional"))
    )
    (net (code "53") (name "Net-(IC3-P0.2)") (class "Default")
      (node (ref "IC3") (pin "19") (pinfunction "P0.2_19") (pintype "bidirectional"))
      (node (ref "R25") (pin "2") (pinfunction "2_2") (pintype "passive"))
    )
    (net (code "54") (name "Net-(IC3-P3.1{slash}XTAL1)") (class "Default")
      (node (ref "IC3") (pin "6") (pinfunction "P3.1/XTAL1_6") (pintype "bidirectional"))
      (node (ref "Q1") (pin "3") (pinfunction "FO_3") (pintype "output"))
    )
    (net (code "55") (name "Net-(IC4-WP)") (class "Default")
      (node (ref "IC4") (pin "5") (pinfunction "WP_5") (pintype "bidirectional"))
      (node (ref "JP3") (pin "1") (pinfunction "1_1") (pintype "passive"))
      (node (ref "R19") (pin "1") (pinfunction "1_1") (pintype "passive"))
    )
    (net (code "56") (name "Net-(IC5-PIO0_6{slash}SCK0)") (class "Default")
      (node (ref "D50") (pin "C") (pinfunction "C_C") (pintype "passive"))
      (node (ref "IC5") (pin "22") (pinfunction "PIO0_6/SCK0_22") (pintype "bidirectional"))
    )
    (net (code "57") (name "Net-(IC5-PIO0_7{slash}CTS)") (class "Default")
      (node (ref "D51") (pin "C") (pinfunction "C_C") (pintype "passive"))
      (node (ref "IC5") (pin "23") (pinfunction "PIO0_7/CTS_23") (pintype "bidirectional"))
    )
    (net (code "58") (name "Net-(IC5-PIO3_0{slash}DTR{slash}CT16B0_MAT0{slash}TXD)") (class "Default")
      (node (ref "IC5") (pin "36") (pinfunction "PIO3_0/DTR/CT16B0_MAT0/TXD_36") (pintype "bidirectional"))
      (node (ref "R53") (pin "1") (pinfunction "1_1") (pintype "passive"))
    )
    (net (code "59") (name "Net-(IC5-XTALIN)") (class "Default")
      (node (ref "C50") (pin "2") (pinfunction "2_2") (pintype "passive"))
      (node (ref "C56") (pin "2") (pinfunction "2_2") (pintype "passive"))
      (node (ref "IC5") (pin "6") (pinfunction "XTALIN_6") (pintype "input"))
    )
    (net (code "60") (name "Net-(JP2-RXD{slash}IO15)") (class "Default")
      (node (ref "JP2") (pin "10") (pinfunction "RXD/IO15_10") (pintype "passive"))
      (node (ref "R27") (pin "1") (pinfunction "1_1") (pintype "passive"))
    )
    (net (code "61") (name "Net-(JP2-TXD{slash}IO14)") (class "Default")
      (node (ref "JP2") (pin "8") (pinfunction "TXD/IO14_8") (pintype "passive"))
      (node (ref "R26") (pin "1") (pinfunction "1_1") (pintype "passive"))
    )
    (net (code "62") (name "Net-(Q4-FO)") (class "Default")
      (node (ref "C56") (pin "1") (pinfunction "1_1") (pintype "passive"))
      (node (ref "Q4") (pin "3") (pinfunction "FO_3") (pintype "output"))
    )
    (net (code "63") (name "Net-(T1-B)") (class "Default")
      (node (ref "R5") (pin "2") (pinfunction "2_2") (pintype "passive"))
      (node (ref "R6") (pin "2") (pinfunction "2_2") (pintype "passive"))
      (node (ref "R7") (pin "1") (pinfunction "1_1") (pintype "passive"))
      (node (ref "T1") (pin "1") (pinfunction "B_1") (pintype "passive"))
    )
    (net (code "64") (name "Net-(T2-B)") (class "Default")
      (node (ref "C5") (pin "2") (pinfunction "2_2") (pintype "passive"))
      (node (ref "R10") (pin "2") (pinfunction "2_2") (pintype "passive"))
      (node (ref "R11") (pin "1") (pinfunction "1_1") (pintype "passive"))
      (node (ref "T2") (pin "1") (pinfunction "B_1") (pintype "passive"))
    )
    (net (code "65") (name "Net-(T3-B)") (class "Default")
      (node (ref "R13") (pin "2") (pinfunction "2_2") (pintype "passive"))
      (node (ref "R14") (pin "1") (pinfunction "1_1") (pintype "passive"))
      (node (ref "T3") (pin "1") (pinfunction "B_1") (pintype "passive"))
    )
    (net (code "66") (name "Net-(T3-C)") (class "Default")
      (node (ref "R12") (pin "1") (pinfunction "1_1") (pintype "passive"))
      (node (ref "T3") (pin "3") (pinfunction "C_3") (pintype "passive"))
    )
    (net (code "67") (name "Net-(T3-E)") (class "Default")
      (node (ref "R9") (pin "2") (pinfunction "2_2") (pintype "passive"))
      (node (ref "T2") (pin "2") (pinfunction "C_2") (pintype "passive"))
      (node (ref "T2") (pin "4") (pinfunction "C_4") (pintype "passive"))
      (node (ref "T3") (pin "2") (pinfunction "E_2") (pintype "passive"))
    )
    (net (code "68") (name "RST") (class "Default")
      (node (ref "C8") (pin "2") (pinfunction "2_2") (pintype "passive"))
      (node (ref "IC3") (pin "4") (pinfunction "P1.5/RST_4") (pintype "input"))
      (node (ref "ISP") (pin "3") (pinfunction "3_3") (pintype "passive"))
      (node (ref "R17") (pin "1") (pinfunction "1_1") (pintype "passive"))
    )
    (net (code "69") (name "RXD") (class "Default")
      (node (ref "IC3") (pin "11") (pinfunction "P1.1/RXD_11") (pintype "bidirectional"))
      (node (ref "IC5") (pin "37") (pinfunction "PIO3_1/DSR/CT16B0_MAT1/RXD_37") (pintype "bidirectional"))
      (node (ref "ISP") (pin "5") (pinfunction "5_5") (pintype "passive"))
      (node (ref "R26") (pin "2") (pinfunction "2_2") (pintype "passive"))
    )
    (net (code "70") (name "SCL") (class "Default")
      (node (ref "JP2") (pin "5") (pinfunction "IO3/SCL_5") (pintype "passive"))
    )
    (net (code "71") (name "SDA") (class "Default")
      (node (ref "JP2") (pin "3") (pinfunction "IO2/SDA_3") (pintype "passive"))
    )
    (net (code "72") (name "TXD") (class "Default")
      (node (ref "IC3") (pin "12") (pinfunction "P1.0/TXD_12") (pintype "bidirectional"))
      (node (ref "ISP") (pin "4") (pinfunction "4_4") (pintype "passive"))
      (node (ref "R27") (pin "2") (pinfunction "2_2") (pintype "passive"))
      (node (ref "R53") (pin "2") (pinfunction "2_2") (pintype "passive"))
    )
    (net (code "73") (name "V+") (class "Default")
      (node (ref "C4") (pin "1") (pinfunction "1_1") (pintype "passive"))
      (node (ref "C5") (pin "1") (pinfunction "1_1") (pintype "passive"))
      (node (ref "D3") (pin "C") (pinfunction "C_C") (pintype "passive"))
      (node (ref "R10") (pin "1") (pinfunction "1_1") (pintype "passive"))
      (node (ref "R4") (pin "2") (pinfunction "2_2") (pintype "passive"))
      (node (ref "T2") (pin "3") (pinfunction "E_3") (pintype "passive"))
    )
    (net (code "74") (name "VDC") (class "Default")
      (node (ref "C1") (pin "+") (pinfunction "+_+") (pintype "passive"))
      (node (ref "D6") (pin "A") (pinfunction "A_A") (pintype "passive"))
      (node (ref "IC1") (pin "6") (pinfunction "VCC_6") (pintype "power_in"))
      (node (ref "L1") (pin "1") (pinfunction "1_1") (pintype "passive"))
      (node (ref "R1") (pin "1") (pinfunction "1_1") (pintype "passive"))
    )
    (net (code "75") (name "unconnected-(IC3-P0.3-Pad18)") (class "Default")
      (node (ref "IC3") (pin "18") (pinfunction "P0.3_18") (pintype "bidirectional"))
    )
    (net (code "76") (name "unconnected-(IC3-P0.4-Pad17)") (class "Default")
      (node (ref "IC3") (pin "17") (pinfunction "P0.4_17") (pintype "bidirectional"))
    )
    (net (code "77") (name "unconnected-(IC3-P0.5-Pad16)") (class "Default")
      (node (ref "IC3") (pin "16") (pinfunction "P0.5_16") (pintype "bidirectional"))
    )
    (net (code "78") (name "unconnected-(IC3-P0.6-Pad14)") (class "Default")
      (node (ref "IC3") (pin "14") (pinfunction "P0.6_14") (pintype "bidirectional"))
    )
    (net (code "79") (name "unconnected-(IC3-P0.7-Pad13)") (class "Default")
      (node (ref "IC3") (pin "13") (pinfunction "P0.7_13") (pintype "passive"))
    )
    (net (code "80") (name "unconnected-(IC3-P1.2{slash}T0{slash}SCL-Pad10)") (class "Default")
      (node (ref "IC3") (pin "10") (pinfunction "P1.2/T0/SCL_10") (pintype "bidirectional"))
    )
    (net (code "81") (name "unconnected-(IC3-P1.3{slash}INT0{slash}SDA-Pad9)") (class "Default")
      (node (ref "IC3") (pin "9") (pinfunction "P1.3/INT0/SDA_9") (pintype "bidirectional"))
    )
    (net (code "82") (name "unconnected-(IC3-P1.7-Pad2)") (class "Default")
      (node (ref "IC3") (pin "2") (pinfunction "P1.7_2") (pintype "bidirectional"))
    )
    (net (code "83") (name "unconnected-(IC3-P3.0{slash}XTAL2-Pad7)") (class "Default")
      (node (ref "IC3") (pin "7") (pinfunction "P3.0/XTAL2_7") (pintype "bidirectional"))
    )
    (net (code "84") (name "unconnected-(IC5-PIO0_2{slash}SSEL0{slash}CT16B0_CAP0-Pad10)") (class "Default")
      (node (ref "IC5") (pin "10") (pinfunction "PIO0_2/SSEL0/CT16B0_CAP0_10") (pintype "bidirectional"))
    )
    (net (code "85") (name "unconnected-(IC5-PIO0_3-Pad14)") (class "Default")
      (node (ref "IC5") (pin "14") (pinfunction "PIO0_3_14") (pintype "bidirectional"))
    )
    (net (code "86") (name "unconnected-(IC5-PIO1_11{slash}AD7{slash}CT32B1_CAP1-Pad42)") (class "Default")
      (node (ref "IC5") (pin "42") (pinfunction "PIO1_11/AD7/CT32B1_CAP1_42") (pintype "bidirectional"))
    )
    (net (code "87") (name "unconnected-(IC5-PIO2_1{slash}DSR{slash}SCK1-Pad13)") (class "Default")
      (node (ref "IC5") (pin "13") (pinfunction "PIO2_1/DSR/SCK1_13") (pintype "bidirectional"))
    )
    (net (code "88") (name "unconnected-(IC5-PIO2_4{slash}CT16B1_MAT1{slash}SSEL1-Pad19)") (class "Default")
      (node (ref "IC5") (pin "19") (pinfunction "PIO2_4/CT16B1_MAT1/SSEL1_19") (pintype "bidirectional"))
    )
    (net (code "89") (name "unconnected-(IC5-PIO2_5{slash}CT32B0_MAT0-Pad20)") (class "Default")
      (node (ref "IC5") (pin "20") (pinfunction "PIO2_5/CT32B0_MAT0_20") (pintype "bidirectional"))
    )
    (net (code "90") (name "unconnected-(IC5-PIO2_6{slash}CT32B0_MAT1-Pad1)") (class "Default")
      (node (ref "IC5") (pin "1") (pinfunction "PIO2_6/CT32B0_MAT1_1") (pintype "bidirectional"))
    )
    (net (code "91") (name "unconnected-(IC5-PIO2_7{slash}CT32B0_MAT2{slash}RXD-Pad11)") (class "Default")
      (node (ref "IC5") (pin "11") (pinfunction "PIO2_7/CT32B0_MAT2/RXD_11") (pintype "bidirectional"))
    )
    (net (code "92") (name "unconnected-(IC5-PIO2_8{slash}CT32B0_MAT3{slash}TXD-Pad12)") (class "Default")
      (node (ref "IC5") (pin "12") (pinfunction "PIO2_8/CT32B0_MAT3/TXD_12") (pintype "bidirectional"))
    )
    (net (code "93") (name "unconnected-(IC5-PIO2_10-Pad25)") (class "Default")
      (node (ref "IC5") (pin "25") (pinfunction "PIO2_10_25") (pintype "bidirectional"))
    )
    (net (code "94") (name "unconnected-(IC5-PIO3_3{slash}RI{slash}CT16B0_CAP0-Pad48)") (class "Default")
      (node (ref "IC5") (pin "48") (pinfunction "PIO3_3/RI/CT16B0_CAP0_48") (pintype "bidirectional"))
    )
    (net (code "95") (name "unconnected-(IC5-PIO3_4{slash}CT16B0_CAP1{slash}RXD-Pad18)") (class "Default")
      (node (ref "IC5") (pin "18") (pinfunction "PIO3_4/CT16B0_CAP1/RXD_18") (pintype "bidirectional"))
    )
    (net (code "96") (name "unconnected-(IC5-PIO3_5{slash}CT16B1_CAP1{slash}TXD-Pad21)") (class "Default")
      (node (ref "IC5") (pin "21") (pinfunction "PIO3_5/CT16B1_CAP1/TXD_21") (pintype "bidirectional"))
    )
    (net (code "97") (name "unconnected-(IC5-XTALOUT-Pad7)") (class "Default")
      (node (ref "IC5") (pin "7") (pinfunction "XTALOUT_7") (pintype "output"))
    )
    (net (code "98") (name "unconnected-(JP2-5V-Pad2)") (class "Default")
      (node (ref "JP2") (pin "2") (pinfunction "5V_2") (pintype "passive"))
    )
    (net (code "99") (name "unconnected-(JP2-5V-Pad4)") (class "Default")
      (node (ref "JP2") (pin "4") (pinfunction "5V_4") (pintype "passive"))
    )
    (net (code "100") (name "unconnected-(JP2-CE0{slash}IO8-Pad24)") (class "Default")
      (node (ref "JP2") (pin "24") (pinfunction "CE0/IO8_24") (pintype "passive"))
    )
    (net (code "101") (name "unconnected-(JP2-CE1{slash}IO7-Pad26)") (class "Default")
      (node (ref "JP2") (pin "26") (pinfunction "CE1/IO7_26") (pintype "passive"))
    )
    (net (code "102") (name "unconnected-(JP2-IO4-Pad7)") (class "Default")
      (node (ref "JP2") (pin "7") (pinfunction "IO4_7") (pintype "passive"))
    )
    (net (code "103") (name "unconnected-(JP2-IO5-Pad29)") (class "Default")
      (node (ref "JP2") (pin "29") (pinfunction "IO5_29") (pintype "bidirectional"))
    )
    (net (code "104") (name "unconnected-(JP2-IO6-Pad31)") (class "Default")
      (node (ref "JP2") (pin "31") (pinfunction "IO6_31") (pintype "bidirectional"))
    )
    (net (code "105") (name "unconnected-(JP2-IO9{slash}MISO-Pad21)") (class "Default")
      (node (ref "JP2") (pin "21") (pinfunction "IO9/MISO_21") (pintype "passive"))
    )
    (net (code "106") (name "unconnected-(JP2-IO10{slash}MOSI-Pad19)") (class "Default")
      (node (ref "JP2") (pin "19") (pinfunction "IO10/MOSI_19") (pintype "passive"))
    )
    (net (code "107") (name "unconnected-(JP2-IO11{slash}SCK-Pad23)") (class "Default")
      (node (ref "JP2") (pin "23") (pinfunction "IO11/SCK_23") (pintype "passive"))
    )
    (net (code "108") (name "unconnected-(JP2-IO12-Pad32)") (class "Default")
      (node (ref "JP2") (pin "32") (pinfunction "IO12_32") (pintype "bidirectional"))
    )
    (net (code "109") (name "unconnected-(JP2-IO13-Pad33)") (class "Default")
      (node (ref "JP2") (pin "33") (pinfunction "IO13_33") (pintype "bidirectional"))
    )
    (net (code "110") (name "unconnected-(JP2-IO16-Pad36)") (class "Default")
      (node (ref "JP2") (pin "36") (pinfunction "IO16_36") (pintype "bidirectional"))
    )
    (net (code "111") (name "unconnected-(JP2-IO17-Pad11)") (class "Default")
      (node (ref "JP2") (pin "11") (pinfunction "IO17_11") (pintype "passive"))
    )
    (net (code "112") (name "unconnected-(JP2-IO19-Pad35)") (class "Default")
      (node (ref "JP2") (pin "35") (pinfunction "IO19_35") (pintype "bidirectional"))
    )
    (net (code "113") (name "unconnected-(JP2-IO20-Pad38)") (class "Default")
      (node (ref "JP2") (pin "38") (pinfunction "IO20_38") (pintype "bidirectional"))
    )
    (net (code "114") (name "unconnected-(JP2-IO21-Pad40)") (class "Default")
      (node (ref "JP2") (pin "40") (pinfunction "IO21_40") (pintype "bidirectional"))
    )
    (net (code "115") (name "unconnected-(JP2-IO22-Pad15)") (class "Default")
      (node (ref "JP2") (pin "15") (pinfunction "IO22_15") (pintype "passive"))
    )
    (net (code "116") (name "unconnected-(JP2-IO23-Pad16)") (class "Default")
      (node (ref "JP2") (pin "16") (pinfunction "IO23_16") (pintype "passive"))
    )
    (net (code "117") (name "unconnected-(JP2-IO24-Pad18)") (class "Default")
      (node (ref "JP2") (pin "18") (pinfunction "IO24_18") (pintype "passive"))
    )
    (net (code "118") (name "unconnected-(JP2-IO25-Pad22)") (class "Default")
      (node (ref "JP2") (pin "22") (pinfunction "IO25_22") (pintype "passive"))
    )
    (net (code "119") (name "unconnected-(JP2-IO26-Pad37)") (class "Default")
      (node (ref "JP2") (pin "37") (pinfunction "IO26_37") (pintype "bidirectional"))
    )
    (net (code "120") (name "unconnected-(JP2-IO27-Pad13)") (class "Default")
      (node (ref "JP2") (pin "13") (pinfunction "IO27_13") (pintype "passive"))
    )
    (net (code "121") (name "unconnected-(JP2-PWM{slash}IO18-Pad12)") (class "Default")
      (node (ref "JP2") (pin "12") (pinfunction "PWM/IO18_12") (pintype "passive"))
    )
    (net (code "122") (name "unconnected-(JP7-Pad6)") (class "Default")
      (node (ref "JP7") (pin "6") (pinfunction "6_6") (pintype "passive"))
    )
    (net (code "123") (name "unconnected-(JP7-Pad8)") (class "Default")
      (node (ref "JP7") (pin "8") (pinfunction "8_8") (pintype "passive"))
    )
  )
)
